# 04A-020.net
KiCad netlist of a schematic drawn in EAGLE
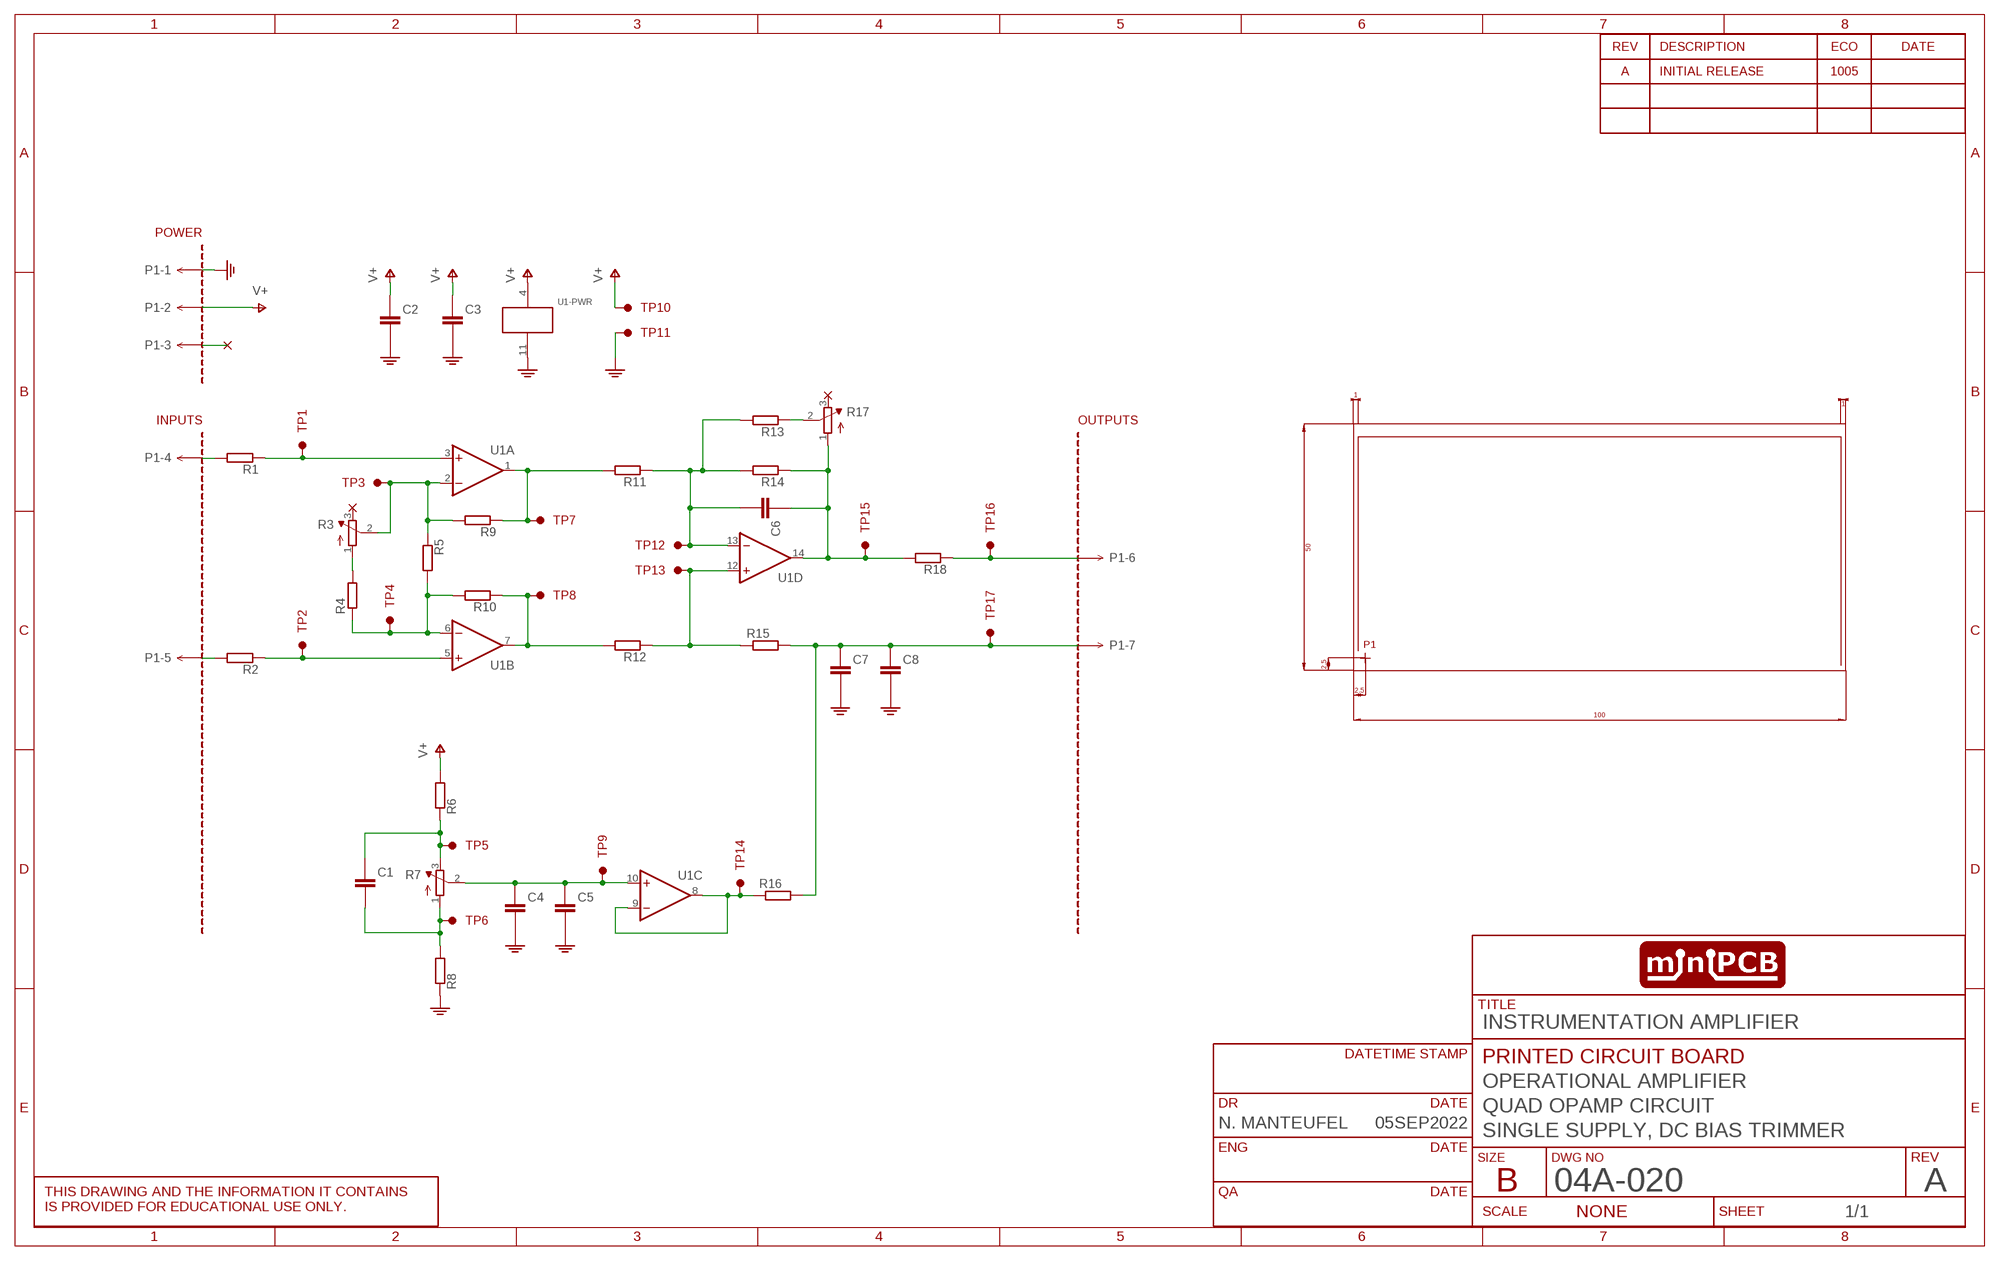
[diagram p0: schematic, sheet 1]

(export (version "E")
  (design (tool "Eeschema 10.0.6"))
  (components
    (comp (ref "C1")
      (value "CAPACITORTHD")
      (footprint "eagle-import:C050-024X044")
      (libsource (lib "eagle-import") (part "CAPACITORTHD"))
    )
    (comp (ref "C2")
      (value "CAPACITOR_10")
      (footprint "eagle-import:C5MM")
      (libsource (lib "eagle-import") (part "CAPACITOR_10"))
    )
    (comp (ref "C3")
      (value "CAPACITORTHD")
      (footprint "eagle-import:C050-024X044")
      (libsource (lib "eagle-import") (part "CAPACITORTHD"))
    )
    (comp (ref "C4")
      (value "CAPACITOR_10")
      (footprint "eagle-import:C5MM")
      (libsource (lib "eagle-import") (part "CAPACITOR_10"))
    )
    (comp (ref "C5")
      (value "CAPACITORTHD")
      (footprint "eagle-import:C050-024X044")
      (libsource (lib "eagle-import") (part "CAPACITORTHD"))
    )
    (comp (ref "C6")
      (value "CAPACITORTHD")
      (footprint "eagle-import:C050-024X044")
      (libsource (lib "eagle-import") (part "CAPACITORTHD"))
    )
    (comp (ref "C7")
      (value "CAPACITOR_10")
      (footprint "eagle-import:C5MM")
      (libsource (lib "eagle-import") (part "CAPACITOR_10"))
    )
    (comp (ref "C8")
      (value "CAPACITORTHD")
      (footprint "eagle-import:C050-024X044")
      (libsource (lib "eagle-import") (part "CAPACITORTHD"))
    )
    (comp (ref "P1")
      (value "MINIPCB_7P")
      (footprint "eagle-import:PINS_1X7")
      (libsource (lib "eagle-import") (part "MINIPCB_7P"))
    )
    (comp (ref "R1")
      (value "RESISTOR10MM")
      (footprint "eagle-import:0207_10")
      (libsource (lib "eagle-import") (part "RESISTOR10MM"))
    )
    (comp (ref "R2")
      (value "RESISTOR10MM")
      (footprint "eagle-import:0207_10")
      (libsource (lib "eagle-import") (part "RESISTOR10MM"))
    )
    (comp (ref "R3")
      (value "TRIMPOT0.100THD")
      (footprint "eagle-import:TRIM_0100")
      (libsource (lib "eagle-import") (part "TRIMPOT0.100THD"))
    )
    (comp (ref "R4")
      (value "RESISTOR10MM")
      (footprint "eagle-import:0207_10")
      (libsource (lib "eagle-import") (part "RESISTOR10MM"))
    )
    (comp (ref "R5")
      (value "RESISTOR10MM")
      (footprint "eagle-import:0207_10")
      (libsource (lib "eagle-import") (part "RESISTOR10MM"))
    )
    (comp (ref "R6")
      (value "RESISTOR10MM")
      (footprint "eagle-import:0207_10")
      (libsource (lib "eagle-import") (part "RESISTOR10MM"))
    )
    (comp (ref "R7")
      (value "TRIMPOT0.100THD")
      (footprint "eagle-import:TRIM_0100")
      (libsource (lib "eagle-import") (part "TRIMPOT0.100THD"))
    )
    (comp (ref "R8")
      (value "RESISTOR10MM")
      (footprint "eagle-import:0207_10")
      (libsource (lib "eagle-import") (part "RESISTOR10MM"))
    )
    (comp (ref "R9")
      (value "RESISTOR10MM")
      (footprint "eagle-import:0207_10")
      (libsource (lib "eagle-import") (part "RESISTOR10MM"))
    )
    (comp (ref "R10")
      (value "RESISTOR10MM")
      (footprint "eagle-import:0207_10")
      (libsource (lib "eagle-import") (part "RESISTOR10MM"))
    )
    (comp (ref "R11")
      (value "RESISTOR10MM")
      (footprint "eagle-import:0207_10")
      (libsource (lib "eagle-import") (part "RESISTOR10MM"))
    )
    (comp (ref "R12")
      (value "RESISTOR10MM")
      (footprint "eagle-import:0207_10")
      (libsource (lib "eagle-import") (part "RESISTOR10MM"))
    )
    (comp (ref "R13")
      (value "RESISTOR10MM")
      (footprint "eagle-import:0207_10")
      (libsource (lib "eagle-import") (part "RESISTOR10MM"))
    )
    (comp (ref "R14")
      (value "RESISTOR10MM")
      (footprint "eagle-import:0207_10")
      (libsource (lib "eagle-import") (part "RESISTOR10MM"))
    )
    (comp (ref "R15")
      (value "RESISTOR10MM")
      (footprint "eagle-import:0207_10")
      (libsource (lib "eagle-import") (part "RESISTOR10MM"))
    )
    (comp (ref "R16")
      (value "RESISTOR10MM")
      (footprint "eagle-import:0207_10")
      (libsource (lib "eagle-import") (part "RESISTOR10MM"))
    )
    (comp (ref "R17")
      (value "TRIMPOT0.100THD")
      (footprint "eagle-import:TRIM_0100")
      (libsource (lib "eagle-import") (part "TRIMPOT0.100THD"))
    )
    (comp (ref "R18")
      (value "RESISTOR10MM")
      (footprint "eagle-import:0207_10")
      (libsource (lib "eagle-import") (part "RESISTOR10MM"))
    )
    (comp (ref "TP1")
      (value "TESTPOINTKE5000-SMTEXT")
      (footprint "eagle-import:PINS_1_TESTPOINT_KE5000_NOTEXT")
      (libsource (lib "eagle-import") (part "TESTPOINTKE5000-SMTEXT"))
    )
    (comp (ref "TP2")
      (value "TESTPOINTKE5000-SMTEXT")
      (footprint "eagle-import:PINS_1_TESTPOINT_KE5000_NOTEXT")
      (libsource (lib "eagle-import") (part "TESTPOINTKE5000-SMTEXT"))
    )
    (comp (ref "TP3")
      (value "TESTPOINTKE5000-SMTEXT")
      (footprint "eagle-import:PINS_1_TESTPOINT_KE5000_NOTEXT")
      (libsource (lib "eagle-import") (part "TESTPOINTKE5000-SMTEXT"))
    )
    (comp (ref "TP4")
      (value "TESTPOINTKE5000-SMTEXT")
      (footprint "eagle-import:PINS_1_TESTPOINT_KE5000_NOTEXT")
      (libsource (lib "eagle-import") (part "TESTPOINTKE5000-SMTEXT"))
    )
    (comp (ref "TP5")
      (value "TESTPOINTKE5000-SMTEXT")
      (footprint "eagle-import:PINS_1_TESTPOINT_KE5000_NOTEXT")
      (libsource (lib "eagle-import") (part "TESTPOINTKE5000-SMTEXT"))
    )
    (comp (ref "TP6")
      (value "TESTPOINTKE5000-SMTEXT")
      (footprint "eagle-import:PINS_1_TESTPOINT_KE5000_NOTEXT")
      (libsource (lib "eagle-import") (part "TESTPOINTKE5000-SMTEXT"))
    )
    (comp (ref "TP7")
      (value "TESTPOINTKE5000-SMTEXT")
      (footprint "eagle-import:PINS_1_TESTPOINT_KE5000_NOTEXT")
      (libsource (lib "eagle-import") (part "TESTPOINTKE5000-SMTEXT"))
    )
    (comp (ref "TP8")
      (value "TESTPOINTKE5000-SMTEXT")
      (footprint "eagle-import:PINS_1_TESTPOINT_KE5000_NOTEXT")
      (libsource (lib "eagle-import") (part "TESTPOINTKE5000-SMTEXT"))
    )
    (comp (ref "TP9")
      (value "TESTPOINTKE5000-SMTEXT")
      (footprint "eagle-import:PINS_1_TESTPOINT_KE5000_NOTEXT")
      (libsource (lib "eagle-import") (part "TESTPOINTKE5000-SMTEXT"))
    )
    (comp (ref "TP10")
      (value "TESTPOINTKE5000-SMTEXT")
      (footprint "eagle-import:PINS_1_TESTPOINT_KE5000_NOTEXT")
      (libsource (lib "eagle-import") (part "TESTPOINTKE5000-SMTEXT"))
    )
    (comp (ref "TP11")
      (value "TESTPOINTKE5000-SMTEXT")
      (footprint "eagle-import:PINS_1_TESTPOINT_KE5000_NOTEXT")
      (libsource (lib "eagle-import") (part "TESTPOINTKE5000-SMTEXT"))
    )
    (comp (ref "TP12")
      (value "TESTPOINTKE5000-SMTEXT")
      (footprint "eagle-import:PINS_1_TESTPOINT_KE5000_NOTEXT")
      (libsource (lib "eagle-import") (part "TESTPOINTKE5000-SMTEXT"))
    )
    (comp (ref "TP13")
      (value "TESTPOINTKE5000-SMTEXT")
      (footprint "eagle-import:PINS_1_TESTPOINT_KE5000_NOTEXT")
      (libsource (lib "eagle-import") (part "TESTPOINTKE5000-SMTEXT"))
    )
    (comp (ref "TP14")
      (value "TESTPOINTKE5000-SMTEXT")
      (footprint "eagle-import:PINS_1_TESTPOINT_KE5000_NOTEXT")
      (libsource (lib "eagle-import") (part "TESTPOINTKE5000-SMTEXT"))
    )
    (comp (ref "TP15")
      (value "TESTPOINTKE5000-SMTEXT")
      (footprint "eagle-import:PINS_1_TESTPOINT_KE5000_NOTEXT")
      (libsource (lib "eagle-import") (part "TESTPOINTKE5000-SMTEXT"))
    )
    (comp (ref "TP16")
      (value "TESTPOINTKE5000-SMTEXT")
      (footprint "eagle-import:PINS_1_TESTPOINT_KE5000_NOTEXT")
      (libsource (lib "eagle-import") (part "TESTPOINTKE5000-SMTEXT"))
    )
    (comp (ref "TP17")
      (value "TESTPOINTKE5000-SMTEXT")
      (footprint "eagle-import:PINS_1_TESTPOINT_KE5000_NOTEXT")
      (libsource (lib "eagle-import") (part "TESTPOINTKE5000-SMTEXT"))
    )
    (comp (ref "U1")
      (value "OPAMP_QUADTHD")
      (footprint "eagle-import:DIL14")
      (libsource (lib "eagle-import") (part "OPAMP_QUADTHD"))
    )
    (comp (ref "U2")
      (value "CLASSIC-50X100")
      (footprint "eagle-import:PCB50X100")
      (fields
        (field (name "PART_NUMBER") "04A-020")
        (field (name "TITLE") "miniPCB, INSTRUMENTATION AMPLIFIER")
      )
      (libsource (lib "eagle-import") (part "CLASSIC-50X100"))
    )
  )
  (nets
    (net (code "1") (name "GND") (class "Default")
      (node (ref "C2") (pin "-") (pinfunction "-_-") (pintype "passive"))
      (node (ref "C3") (pin "2") (pinfunction "-_2") (pintype "passive"))
      (node (ref "C4") (pin "-") (pinfunction "-_-") (pintype "passive"))
      (node (ref "C5") (pin "2") (pinfunction "-_2") (pintype "passive"))
      (node (ref "C7") (pin "-") (pinfunction "-_-") (pintype "passive"))
      (node (ref "C8") (pin "2") (pinfunction "-_2") (pintype "passive"))
      (node (ref "P1") (pin "1") (pinfunction "1_1") (pintype "bidirectional"))
      (node (ref "R8") (pin "1") (pinfunction "1_1") (pintype "passive"))
      (node (ref "TP11") (pin "1") (pinfunction "1_1") (pintype "bidirectional"))
      (node (ref "U1") (pin "11") (pinfunction "V-_11") (pintype "power_in"))
    )
    (net (code "2") (name "Net-(C1-+)") (class "Default")
      (node (ref "C1") (pin "1") (pinfunction "+_1") (pintype "passive"))
      (node (ref "R6") (pin "1") (pinfunction "1_1") (pintype "passive"))
      (node (ref "R7") (pin "3") (pinfunction "E_3") (pintype "passive"))
      (node (ref "TP5") (pin "1") (pinfunction "1_1") (pintype "bidirectional"))
    )
    (net (code "3") (name "Net-(C1--)") (class "Default")
      (node (ref "C1") (pin "2") (pinfunction "-_2") (pintype "passive"))
      (node (ref "R7") (pin "1") (pinfunction "A_1") (pintype "passive"))
      (node (ref "R8") (pin "2") (pinfunction "2_2") (pintype "passive"))
      (node (ref "TP6") (pin "1") (pinfunction "1_1") (pintype "bidirectional"))
    )
    (net (code "4") (name "Net-(C5-+)") (class "Default")
      (node (ref "C4") (pin "+") (pinfunction "+_+") (pintype "passive"))
      (node (ref "C5") (pin "1") (pinfunction "+_1") (pintype "passive"))
      (node (ref "R7") (pin "2") (pinfunction "S_2") (pintype "passive"))
      (node (ref "TP9") (pin "1") (pinfunction "1_1") (pintype "bidirectional"))
      (node (ref "U1") (pin "10") (pinfunction "+IN_10") (pintype "input"))
    )
    (net (code "5") (name "Net-(C6-+)") (class "Default")
      (node (ref "C6") (pin "1") (pinfunction "+_1") (pintype "passive"))
      (node (ref "R14") (pin "1") (pinfunction "1_1") (pintype "passive"))
      (node (ref "R17") (pin "1") (pinfunction "A_1") (pintype "passive"))
      (node (ref "R18") (pin "2") (pinfunction "2_2") (pintype "passive"))
      (node (ref "TP15") (pin "1") (pinfunction "1_1") (pintype "bidirectional"))
      (node (ref "U1") (pin "14") (pinfunction "OUT_14") (pintype "output"))
    )
    (net (code "6") (name "Net-(C6--)") (class "Default")
      (node (ref "C6") (pin "2") (pinfunction "-_2") (pintype "passive"))
      (node (ref "R11") (pin "1") (pinfunction "1_1") (pintype "passive"))
      (node (ref "R13") (pin "2") (pinfunction "2_2") (pintype "passive"))
      (node (ref "R14") (pin "2") (pinfunction "2_2") (pintype "passive"))
      (node (ref "TP12") (pin "1") (pinfunction "1_1") (pintype "bidirectional"))
      (node (ref "U1") (pin "13") (pinfunction "-IN_13") (pintype "input"))
    )
    (net (code "7") (name "Net-(C8-+)") (class "Default")
      (node (ref "C7") (pin "+") (pinfunction "+_+") (pintype "passive"))
      (node (ref "C8") (pin "1") (pinfunction "+_1") (pintype "passive"))
      (node (ref "P1") (pin "7") (pinfunction "1_7") (pintype "bidirectional"))
      (node (ref "R15") (pin "2") (pinfunction "2_2") (pintype "passive"))
      (node (ref "R16") (pin "2") (pinfunction "2_2") (pintype "passive"))
      (node (ref "TP17") (pin "1") (pinfunction "1_1") (pintype "bidirectional"))
    )
    (net (code "8") (name "Net-(P1D-1)") (class "Default")
      (node (ref "P1") (pin "4") (pinfunction "1_4") (pintype "bidirectional"))
      (node (ref "R1") (pin "2") (pinfunction "2_2") (pintype "passive"))
    )
    (net (code "9") (name "Net-(P1E-1)") (class "Default")
      (node (ref "P1") (pin "5") (pinfunction "1_5") (pintype "bidirectional"))
      (node (ref "R2") (pin "2") (pinfunction "2_2") (pintype "passive"))
    )
    (net (code "10") (name "Net-(P1F-1)") (class "Default")
      (node (ref "P1") (pin "6") (pinfunction "1_6") (pintype "bidirectional"))
      (node (ref "R18") (pin "1") (pinfunction "1_1") (pintype "passive"))
      (node (ref "TP16") (pin "1") (pinfunction "1_1") (pintype "bidirectional"))
    )
    (net (code "11") (name "Net-(R3-A)") (class "Default")
      (node (ref "R3") (pin "1") (pinfunction "A_1") (pintype "passive"))
      (node (ref "R4") (pin "2") (pinfunction "2_2") (pintype "passive"))
    )
    (net (code "12") (name "Net-(R3-S)") (class "Default")
      (node (ref "R3") (pin "2") (pinfunction "S_2") (pintype "passive"))
      (node (ref "R5") (pin "1") (pinfunction "1_1") (pintype "passive"))
      (node (ref "R9") (pin "2") (pinfunction "2_2") (pintype "passive"))
      (node (ref "TP3") (pin "1") (pinfunction "1_1") (pintype "bidirectional"))
      (node (ref "U1") (pin "2") (pinfunction "-IN_2") (pintype "input"))
    )
    (net (code "13") (name "Net-(R17-S)") (class "Default")
      (node (ref "R13") (pin "1") (pinfunction "1_1") (pintype "passive"))
      (node (ref "R17") (pin "2") (pinfunction "S_2") (pintype "passive"))
    )
    (net (code "14") (name "Net-(U1B-+IN)") (class "Default")
      (node (ref "R1") (pin "1") (pinfunction "1_1") (pintype "passive"))
      (node (ref "TP1") (pin "1") (pinfunction "1_1") (pintype "bidirectional"))
      (node (ref "U1") (pin "3") (pinfunction "+IN_3") (pintype "input"))
    )
    (net (code "15") (name "Net-(U1B-OUT)") (class "Default")
      (node (ref "R11") (pin "2") (pinfunction "2_2") (pintype "passive"))
      (node (ref "R9") (pin "1") (pinfunction "1_1") (pintype "passive"))
      (node (ref "TP7") (pin "1") (pinfunction "1_1") (pintype "bidirectional"))
      (node (ref "U1") (pin "1") (pinfunction "OUT_1") (pintype "output"))
    )
    (net (code "16") (name "Net-(U1C-+IN)") (class "Default")
      (node (ref "R2") (pin "1") (pinfunction "1_1") (pintype "passive"))
      (node (ref "TP2") (pin "1") (pinfunction "1_1") (pintype "bidirectional"))
      (node (ref "U1") (pin "5") (pinfunction "+IN_5") (pintype "input"))
    )
    (net (code "17") (name "Net-(U1C--IN)") (class "Default")
      (node (ref "R10") (pin "2") (pinfunction "2_2") (pintype "passive"))
      (node (ref "R4") (pin "1") (pinfunction "1_1") (pintype "passive"))
      (node (ref "R5") (pin "2") (pinfunction "2_2") (pintype "passive"))
      (node (ref "TP4") (pin "1") (pinfunction "1_1") (pintype "bidirectional"))
      (node (ref "U1") (pin "6") (pinfunction "-IN_6") (pintype "input"))
    )
    (net (code "18") (name "Net-(U1C-OUT)") (class "Default")
      (node (ref "R10") (pin "1") (pinfunction "1_1") (pintype "passive"))
      (node (ref "R12") (pin "2") (pinfunction "2_2") (pintype "passive"))
      (node (ref "TP8") (pin "1") (pinfunction "1_1") (pintype "bidirectional"))
      (node (ref "U1") (pin "7") (pinfunction "OUT_7") (pintype "output"))
    )
    (net (code "19") (name "Net-(U1D--IN)") (class "Default")
      (node (ref "R16") (pin "1") (pinfunction "1_1") (pintype "passive"))
      (node (ref "TP14") (pin "1") (pinfunction "1_1") (pintype "bidirectional"))
      (node (ref "U1") (pin "8") (pinfunction "OUT_8") (pintype "output"))
      (node (ref "U1") (pin "9") (pinfunction "-IN_9") (pintype "input"))
    )
    (net (code "20") (name "Net-(U1E-+IN)") (class "Default")
      (node (ref "R12") (pin "1") (pinfunction "1_1") (pintype "passive"))
      (node (ref "R15") (pin "1") (pinfunction "1_1") (pintype "passive"))
      (node (ref "TP13") (pin "1") (pinfunction "1_1") (pintype "bidirectional"))
      (node (ref "U1") (pin "12") (pinfunction "+IN_12") (pintype "input"))
    )
    (net (code "21") (name "V+") (class "Default")
      (node (ref "C2") (pin "+") (pinfunction "+_+") (pintype "passive"))
      (node (ref "C3") (pin "1") (pinfunction "+_1") (pintype "passive"))
      (node (ref "P1") (pin "2") (pinfunction "1_2") (pintype "bidirectional"))
      (node (ref "R6") (pin "2") (pinfunction "2_2") (pintype "passive"))
      (node (ref "TP10") (pin "1") (pinfunction "1_1") (pintype "bidirectional"))
      (node (ref "U1") (pin "4") (pinfunction "V+_4") (pintype "power_in"))
    )
    (net (code "22") (name "unconnected-(P1C-1-Pad3)") (class "Default")
      (node (ref "P1") (pin "3") (pinfunction "1_3") (pintype "bidirectional"))
    )
    (net (code "23") (name "unconnected-(R3-E-Pad3)") (class "Default")
      (node (ref "R3") (pin "3") (pinfunction "E_3") (pintype "passive"))
    )
    (net (code "24") (name "unconnected-(R17-E-Pad3)") (class "Default")
      (node (ref "R17") (pin "3") (pinfunction "E_3") (pintype "passive"))
    )
  )
)
